# scm.net
KiCad netlist of a schematic drawn in EAGLE
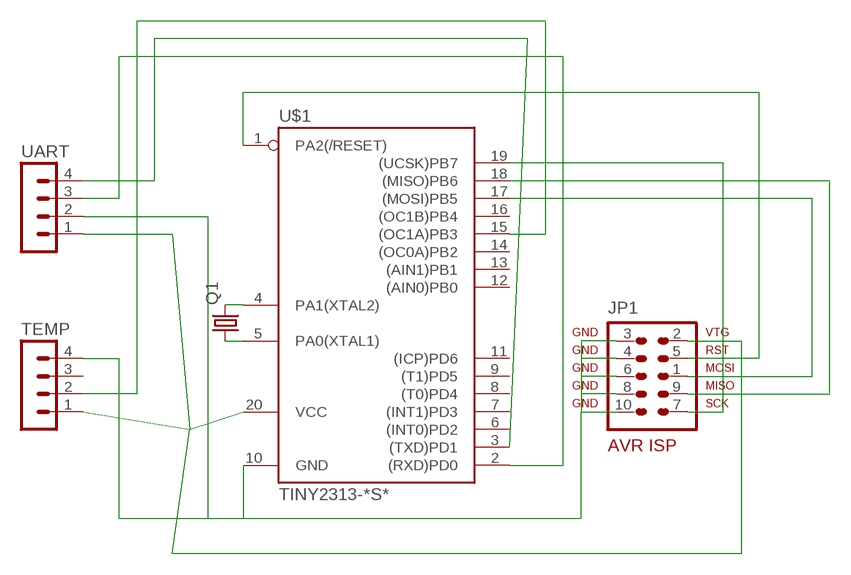
[diagram p0: schematic, sheet 1]

(export (version "E")
  (design (tool "Eeschema 10.0.6"))
  (components
    (comp (ref "JP1")
      (value "AVR-ISP-10")
      (footprint "eagle-import:AVR-ISP-10")
      (libsource (lib "eagle-import") (part "AVR-ISP-10"))
    )
    (comp (ref "Q1")
      (value "CRYSTALHC49U70")
      (footprint "eagle-import:HC49U70")
      (libsource (lib "eagle-import") (part "CRYSTALHC49U70"))
    )
    (comp (ref "TEMP")
      (value "MA04-1")
      (footprint "eagle-import:MA04-1")
      (libsource (lib "eagle-import") (part "MA04-1"))
    )
    (comp (ref "U$1")
      (value "TINY2313-*S*")
      (footprint "eagle-import:SO20L$")
      (libsource (lib "eagle-import") (part "TINY2313-S"))
    )
    (comp (ref "UART")
      (value "MA04-1")
      (footprint "eagle-import:MA04-1")
      (libsource (lib "eagle-import") (part "MA04-1"))
    )
  )
  (nets
    (net (code "1") (name "Net-(U$1-(MISO)PB6)") (class "Default")
      (node (ref "JP1") (pin "9") (pinfunction "9_9") (pintype "passive"))
      (node (ref "U$1") (pin "18") (pinfunction "(MISO)PB6_18") (pintype "bidirectional"))
    )
    (net (code "2") (name "Net-(U$1-(MOSI)PB5)") (class "Default")
      (node (ref "JP1") (pin "1") (pinfunction "1_1") (pintype "passive"))
      (node (ref "U$1") (pin "17") (pinfunction "(MOSI)PB5_17") (pintype "bidirectional"))
    )
    (net (code "3") (name "Net-(U$1-(OC1A)PB3)") (class "Default")
      (node (ref "TEMP") (pin "2") (pinfunction "2_2") (pintype "passive"))
      (node (ref "U$1") (pin "15") (pinfunction "(OC1A)PB3_15") (pintype "bidirectional"))
    )
    (net (code "4") (name "Net-(U$1-(RXD)PD0)") (class "Default")
      (node (ref "U$1") (pin "2") (pinfunction "(RXD)PD0_2") (pintype "bidirectional"))
      (node (ref "UART") (pin "3") (pinfunction "3_3") (pintype "passive"))
    )
    (net (code "5") (name "Net-(U$1-(TXD)PD1)") (class "Default")
      (node (ref "U$1") (pin "3") (pinfunction "(TXD)PD1_3") (pintype "bidirectional"))
      (node (ref "UART") (pin "4") (pinfunction "4_4") (pintype "passive"))
    )
    (net (code "6") (name "Net-(U$1-(UCSK)PB7)") (class "Default")
      (node (ref "JP1") (pin "7") (pinfunction "7_7") (pintype "passive"))
      (node (ref "U$1") (pin "19") (pinfunction "(UCSK)PB7_19") (pintype "bidirectional"))
    )
    (net (code "7") (name "Net-(U$1-GND)") (class "Default")
      (node (ref "JP1") (pin "10") (pinfunction "10_10") (pintype "passive"))
      (node (ref "JP1") (pin "3") (pinfunction "3_3") (pintype "passive"))
      (node (ref "JP1") (pin "4") (pinfunction "4_4") (pintype "passive"))
      (node (ref "JP1") (pin "6") (pinfunction "6_6") (pintype "passive"))
      (node (ref "JP1") (pin "8") (pinfunction "8_8") (pintype "passive"))
      (node (ref "TEMP") (pin "4") (pinfunction "4_4") (pintype "passive"))
      (node (ref "U$1") (pin "10") (pinfunction "GND_10") (pintype "power_in"))
      (node (ref "UART") (pin "2") (pinfunction "2_2") (pintype "passive"))
    )
    (net (code "8") (name "Net-(U$1-PA0(XTAL1))") (class "Default")
      (node (ref "Q1") (pin "1") (pinfunction "1_1") (pintype "passive"))
      (node (ref "U$1") (pin "5") (pinfunction "PA0(XTAL1)_5") (pintype "bidirectional"))
    )
    (net (code "9") (name "Net-(U$1-PA1(XTAL2))") (class "Default")
      (node (ref "Q1") (pin "2") (pinfunction "2_2") (pintype "passive"))
      (node (ref "U$1") (pin "4") (pinfunction "PA1(XTAL2)_4") (pintype "bidirectional"))
    )
    (net (code "10") (name "Net-(U$1-PA2({slash}RESET))") (class "Default")
      (node (ref "JP1") (pin "5") (pinfunction "5_5") (pintype "passive"))
      (node (ref "U$1") (pin "1") (pinfunction "PA2(/RESET)_1") (pintype "input"))
    )
    (net (code "11") (name "Net-(U$1-VCC)") (class "Default")
      (node (ref "JP1") (pin "2") (pinfunction "2_2") (pintype "passive"))
      (node (ref "TEMP") (pin "1") (pinfunction "1_1") (pintype "passive"))
      (node (ref "U$1") (pin "20") (pinfunction "VCC_20") (pintype "power_in"))
      (node (ref "UART") (pin "1") (pinfunction "1_1") (pintype "passive"))
    )
    (net (code "12") (name "unconnected-(TEMP-Pad3)") (class "Default")
      (node (ref "TEMP") (pin "3") (pinfunction "3_3") (pintype "passive"))
    )
    (net (code "13") (name "unconnected-(U$1-(AIN0)PB0-Pad12)") (class "Default")
      (node (ref "U$1") (pin "12") (pinfunction "(AIN0)PB0_12") (pintype "bidirectional"))
    )
    (net (code "14") (name "unconnected-(U$1-(AIN1)PB1-Pad13)") (class "Default")
      (node (ref "U$1") (pin "13") (pinfunction "(AIN1)PB1_13") (pintype "bidirectional"))
    )
    (net (code "15") (name "unconnected-(U$1-(ICP)PD6-Pad11)") (class "Default")
      (node (ref "U$1") (pin "11") (pinfunction "(ICP)PD6_11") (pintype "bidirectional"))
    )
    (net (code "16") (name "unconnected-(U$1-(INT0)PD2-Pad6)") (class "Default")
      (node (ref "U$1") (pin "6") (pinfunction "(INT0)PD2_6") (pintype "bidirectional"))
    )
    (net (code "17") (name "unconnected-(U$1-(INT1)PD3-Pad7)") (class "Default")
      (node (ref "U$1") (pin "7") (pinfunction "(INT1)PD3_7") (pintype "bidirectional"))
    )
    (net (code "18") (name "unconnected-(U$1-(OC0A)PB2-Pad14)") (class "Default")
      (node (ref "U$1") (pin "14") (pinfunction "(OC0A)PB2_14") (pintype "bidirectional"))
    )
    (net (code "19") (name "unconnected-(U$1-(OC1B)PB4-Pad16)") (class "Default")
      (node (ref "U$1") (pin "16") (pinfunction "(OC1B)PB4_16") (pintype "bidirectional"))
    )
    (net (code "20") (name "unconnected-(U$1-(T0)PD4-Pad8)") (class "Default")
      (node (ref "U$1") (pin "8") (pinfunction "(T0)PD4_8") (pintype "bidirectional"))
    )
    (net (code "21") (name "unconnected-(U$1-(T1)PD5-Pad9)") (class "Default")
      (node (ref "U$1") (pin "9") (pinfunction "(T1)PD5_9") (pintype "bidirectional"))
    )
  )
)
